# L9110_v1_0.net
KiCad netlist of a schematic drawn in EAGLE
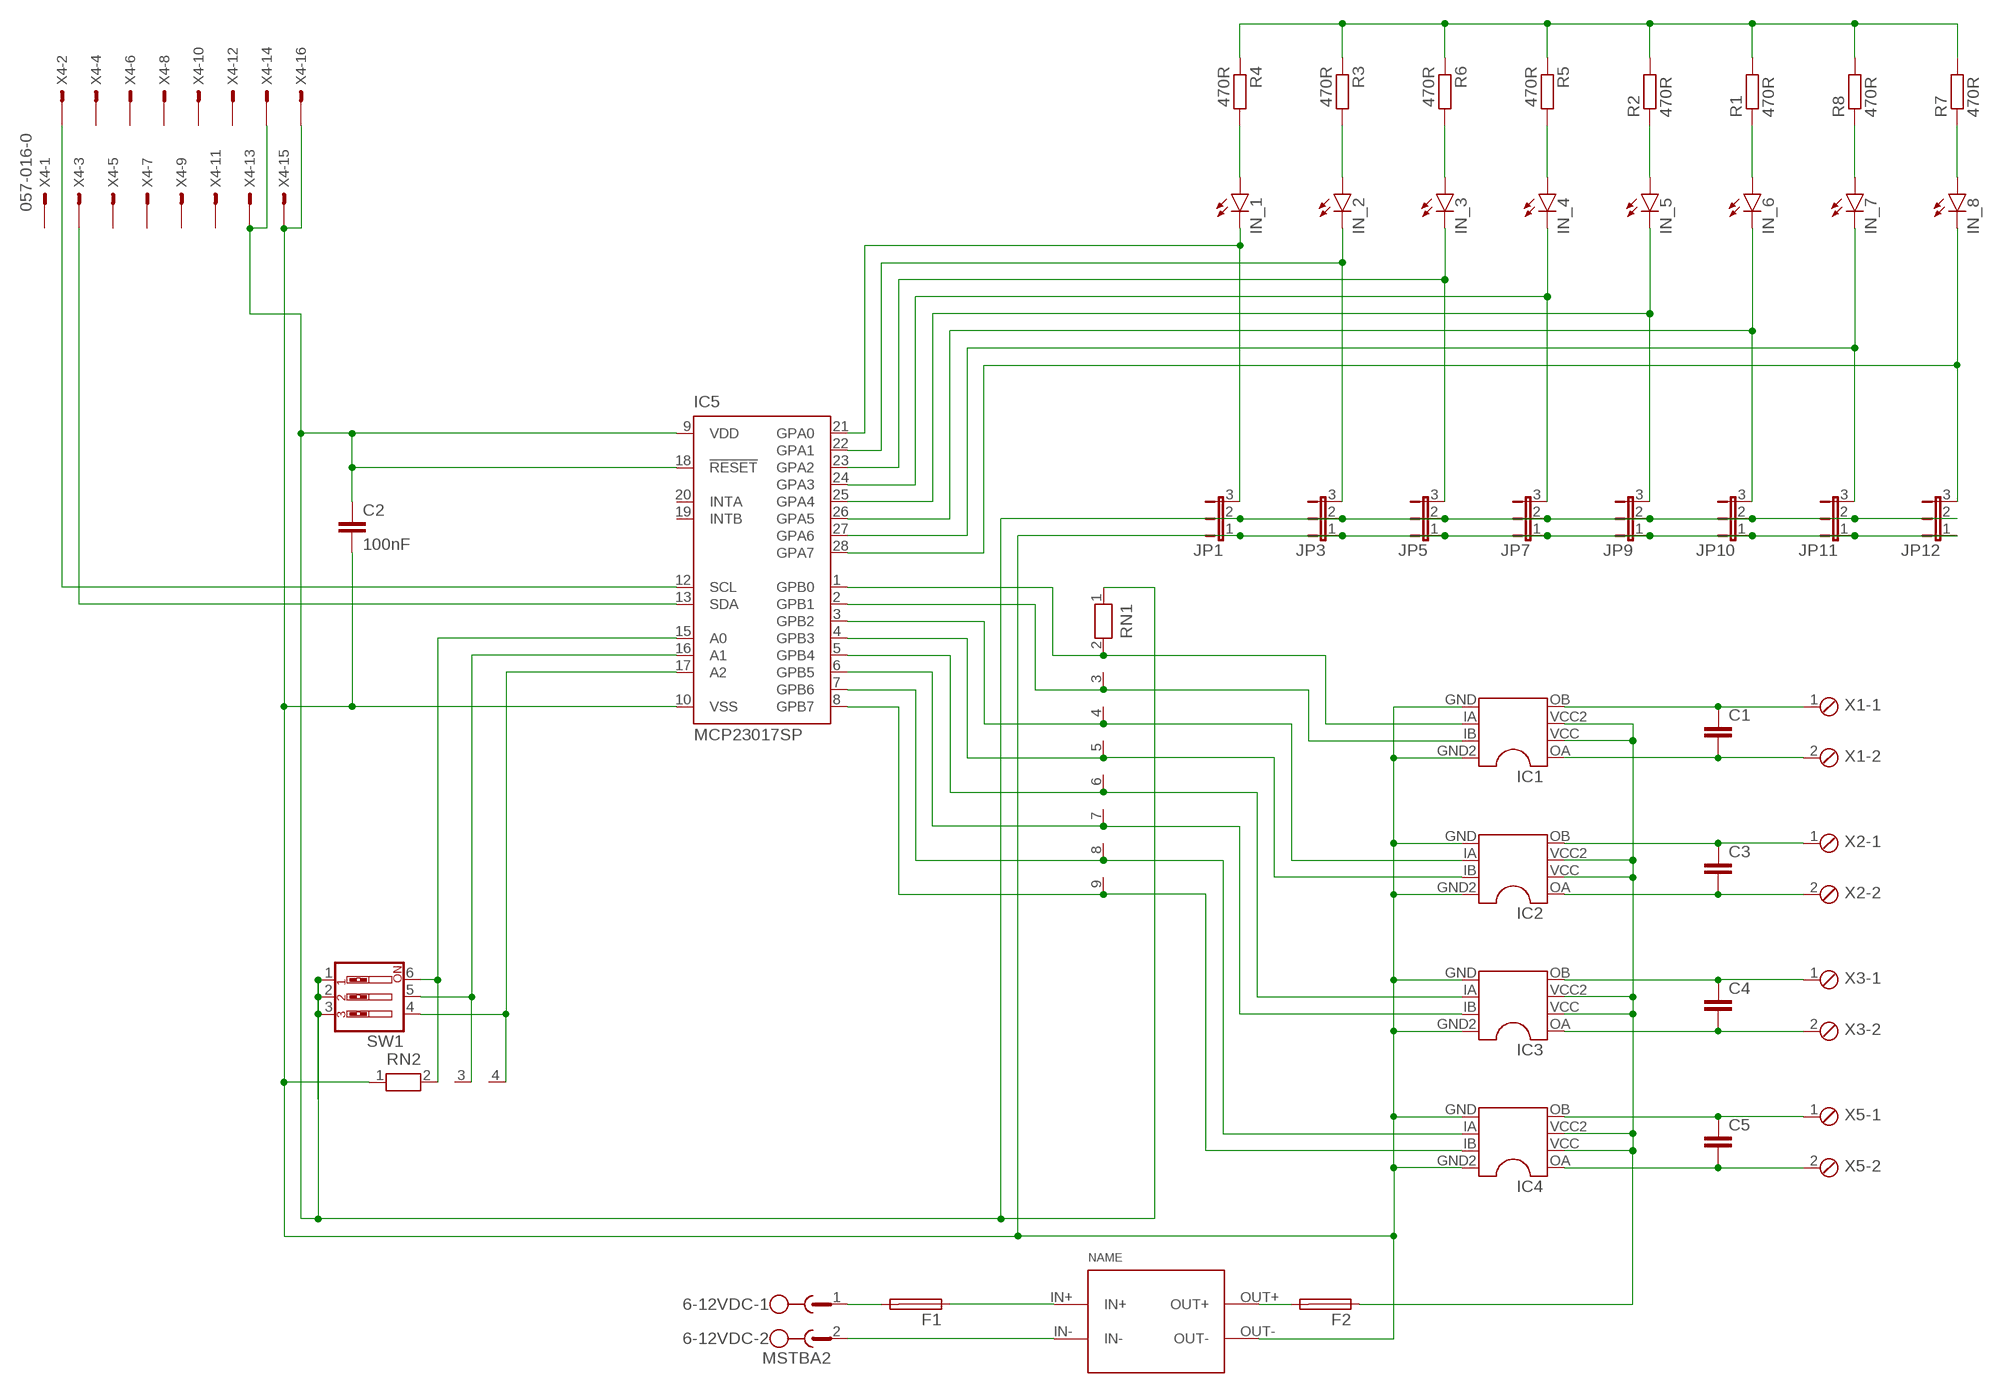
[diagram p0: schematic, sheet 1]

(export (version "E")
  (design (tool "Eeschema 10.0.6"))
  (components
    (comp (ref "6-12VDC")
      (value "MSTBA2")
      (footprint "eagle-import:MSTBA2")
      (fields (field (name "MF") "FARNELL") (field (name "MPN") "1757242"))
      (libsource (lib "eagle-import") (part "MSTBA2"))
    )
    (comp (ref "C1")
      (value "C-EU025-024X044")
      (footprint "eagle-import:C025-024X044")
      (libsource (lib "eagle-import") (part "C-EU025-024X044"))
    )
    (comp (ref "C2")
      (value "100nF")
      (footprint "eagle-import:C025-024X044")
      (libsource (lib "eagle-import") (part "C-EU025-024X044"))
    )
    (comp (ref "C3")
      (value "C-EU025-024X044")
      (footprint "eagle-import:C025-024X044")
      (libsource (lib "eagle-import") (part "C-EU025-024X044"))
    )
    (comp (ref "C4")
      (value "C-EU025-024X044")
      (footprint "eagle-import:C025-024X044")
      (libsource (lib "eagle-import") (part "C-EU025-024X044"))
    )
    (comp (ref "C5")
      (value "C-EU025-024X044")
      (footprint "eagle-import:C025-024X044")
      (libsource (lib "eagle-import") (part "C-EU025-024X044"))
    )
    (comp (ref "F1")
      (value "SH22,5A")
      (footprint "eagle-import:SH22,5A")
      (fields (field (name "MPN") "0031.7701.11"))
      (libsource (lib "eagle-import") (part "SH22,5A"))
    )
    (comp (ref "F2")
      (value "SH22,5A")
      (footprint "eagle-import:SH22,5A")
      (fields (field (name "MPN") "0031.7701.11"))
      (libsource (lib "eagle-import") (part "SH22,5A"))
    )
    (comp (ref "IC1")
      (value "L9110")
      (footprint "eagle-import:L9110")
      (libsource (lib "eagle-import") (part "L9110"))
    )
    (comp (ref "IC2")
      (value "L9110")
      (footprint "eagle-import:L9110")
      (libsource (lib "eagle-import") (part "L9110"))
    )
    (comp (ref "IC3")
      (value "L9110")
      (footprint "eagle-import:L9110")
      (libsource (lib "eagle-import") (part "L9110"))
    )
    (comp (ref "IC4")
      (value "L9110")
      (footprint "eagle-import:L9110")
      (libsource (lib "eagle-import") (part "L9110"))
    )
    (comp (ref "IC5")
      (value "MCP23017SP")
      (footprint "eagle-import:DIL28-3")
      (libsource (lib "eagle-import") (part "MCP23017SP"))
    )
    (comp (ref "IN_1")
      (value "LED3MM")
      (footprint "eagle-import:LED3MM")
      (libsource (lib "eagle-import") (part "LED3MM"))
    )
    (comp (ref "IN_2")
      (value "LED3MM")
      (footprint "eagle-import:LED3MM")
      (libsource (lib "eagle-import") (part "LED3MM"))
    )
    (comp (ref "IN_3")
      (value "LED3MM")
      (footprint "eagle-import:LED3MM")
      (libsource (lib "eagle-import") (part "LED3MM"))
    )
    (comp (ref "IN_4")
      (value "LED3MM")
      (footprint "eagle-import:LED3MM")
      (libsource (lib "eagle-import") (part "LED3MM"))
    )
    (comp (ref "IN_5")
      (value "LED3MM")
      (footprint "eagle-import:LED3MM")
      (libsource (lib "eagle-import") (part "LED3MM"))
    )
    (comp (ref "IN_6")
      (value "LED3MM")
      (footprint "eagle-import:LED3MM")
      (libsource (lib "eagle-import") (part "LED3MM"))
    )
    (comp (ref "IN_7")
      (value "LED3MM")
      (footprint "eagle-import:LED3MM")
      (libsource (lib "eagle-import") (part "LED3MM"))
    )
    (comp (ref "IN_8")
      (value "LED3MM")
      (footprint "eagle-import:LED3MM")
      (libsource (lib "eagle-import") (part "LED3MM"))
    )
    (comp (ref "JP1")
      (value "JP2E")
      (footprint "eagle-import:JP2")
      (libsource (lib "eagle-import") (part "JP2E"))
    )
    (comp (ref "JP3")
      (value "JP2E")
      (footprint "eagle-import:JP2")
      (libsource (lib "eagle-import") (part "JP2E"))
    )
    (comp (ref "JP5")
      (value "JP2E")
      (footprint "eagle-import:JP2")
      (libsource (lib "eagle-import") (part "JP2E"))
    )
    (comp (ref "JP7")
      (value "JP2E")
      (footprint "eagle-import:JP2")
      (libsource (lib "eagle-import") (part "JP2E"))
    )
    (comp (ref "JP9")
      (value "JP2E")
      (footprint "eagle-import:JP2")
      (libsource (lib "eagle-import") (part "JP2E"))
    )
    (comp (ref "JP10")
      (value "JP2E")
      (footprint "eagle-import:JP2")
      (libsource (lib "eagle-import") (part "JP2E"))
    )
    (comp (ref "JP11")
      (value "JP2E")
      (footprint "eagle-import:JP2")
      (libsource (lib "eagle-import") (part "JP2E"))
    )
    (comp (ref "JP12")
      (value "JP2E")
      (footprint "eagle-import:JP2")
      (libsource (lib "eagle-import") (part "JP2E"))
    )
    (comp (ref "R1")
      (value "470R")
      (footprint "eagle-import:0309_10")
      (libsource (lib "eagle-import") (part "R-EU_0309/10"))
    )
    (comp (ref "R2")
      (value "470R")
      (footprint "eagle-import:0309_10")
      (libsource (lib "eagle-import") (part "R-EU_0309/10"))
    )
    (comp (ref "R3")
      (value "470R")
      (footprint "eagle-import:0309_10")
      (libsource (lib "eagle-import") (part "R-EU_0309/10"))
    )
    (comp (ref "R4")
      (value "470R")
      (footprint "eagle-import:0309_10")
      (libsource (lib "eagle-import") (part "R-EU_0309/10"))
    )
    (comp (ref "R5")
      (value "470R")
      (footprint "eagle-import:0309_10")
      (libsource (lib "eagle-import") (part "R-EU_0309/10"))
    )
    (comp (ref "R6")
      (value "470R")
      (footprint "eagle-import:0309_10")
      (libsource (lib "eagle-import") (part "R-EU_0309/10"))
    )
    (comp (ref "R7")
      (value "470R")
      (footprint "eagle-import:0309_10")
      (libsource (lib "eagle-import") (part "R-EU_0309/10"))
    )
    (comp (ref "R8")
      (value "470R")
      (footprint "eagle-import:0309_10")
      (libsource (lib "eagle-import") (part "R-EU_0309/10"))
    )
    (comp (ref "RN1")
      (value "RN08")
      (footprint "eagle-import:RN-9")
      (libsource (lib "eagle-import") (part "RN08"))
    )
    (comp (ref "RN2")
      (value "RN03")
      (footprint "eagle-import:RN-3")
      (libsource (lib "eagle-import") (part "RN03"))
    )
    (comp (ref "SW1")
      (value "SW_DIP-3")
      (footprint "eagle-import:EDG-03")
      (libsource (lib "eagle-import") (part "SW_DIP-3"))
    )
    (comp (ref "U$2")
      (value "CP8-ADJ")
      (footprint "eagle-import:CP8-ADJ")
      (libsource (lib "eagle-import") (part "CP8-ADJ"))
    )
    (comp (ref "X1")
      (value "MPT2")
      (footprint "eagle-import:2POL254")
      (libsource (lib "eagle-import") (part "MPT2"))
    )
    (comp (ref "X2")
      (value "MPT2")
      (footprint "eagle-import:2POL254")
      (libsource (lib "eagle-import") (part "MPT2"))
    )
    (comp (ref "X3")
      (value "MPT2")
      (footprint "eagle-import:2POL254")
      (libsource (lib "eagle-import") (part "MPT2"))
    )
    (comp (ref "X4")
      (value "057-016-0")
      (footprint "eagle-import:057-016-0")
      (libsource (lib "eagle-import") (part "057-016-0"))
    )
    (comp (ref "X5")
      (value "MPT2")
      (footprint "eagle-import:2POL254")
      (libsource (lib "eagle-import") (part "MPT2"))
    )
  )
  (nets
    (net (code "1") (name "Net-(6-12VDC-Pad1)") (class "Default")
      (node (ref "6-12VDC") (pin "1") (pinfunction "1_1") (pintype "passive"))
      (node (ref "F1") (pin "2") (pinfunction "2_2") (pintype "passive"))
    )
    (net (code "2") (name "Net-(6-12VDCB-1)") (class "Default")
      (node (ref "6-12VDC") (pin "2") (pinfunction "1_2") (pintype "passive"))
      (node (ref "U$2") (pin "IN-") (pinfunction "IN-_IN-") (pintype "passive"))
    )
    (net (code "3") (name "Net-(F1-Pad1)") (class "Default")
      (node (ref "F1") (pin "1") (pinfunction "1_1") (pintype "passive"))
      (node (ref "U$2") (pin "IN+") (pinfunction "IN+_IN+") (pintype "passive"))
    )
    (net (code "4") (name "Net-(F2-Pad2)") (class "Default")
      (node (ref "F2") (pin "2") (pinfunction "2_2") (pintype "passive"))
      (node (ref "U$2") (pin "OUT+") (pinfunction "OUT+_OUT+") (pintype "passive"))
    )
    (net (code "5") (name "Net-(IC1-1)") (class "Default")
      (node (ref "C1") (pin "2") (pinfunction "2_2") (pintype "passive"))
      (node (ref "IC1") (pin "OA") (pinfunction "1_OA") (pintype "passive"))
      (node (ref "X1") (pin "2") (pinfunction "1_2") (pintype "passive"))
    )
    (net (code "6") (name "Net-(IC1-2)") (class "Default")
      (node (ref "F2") (pin "1") (pinfunction "1_1") (pintype "passive"))
      (node (ref "IC1") (pin "VCC") (pinfunction "2_VCC") (pintype "passive"))
      (node (ref "IC1") (pin "VCC2") (pinfunction "3_VCC2") (pintype "passive"))
      (node (ref "IC2") (pin "VCC") (pinfunction "2_VCC") (pintype "passive"))
      (node (ref "IC2") (pin "VCC2") (pinfunction "3_VCC2") (pintype "passive"))
      (node (ref "IC3") (pin "VCC") (pinfunction "2_VCC") (pintype "passive"))
      (node (ref "IC3") (pin "VCC2") (pinfunction "3_VCC2") (pintype "passive"))
      (node (ref "IC4") (pin "VCC") (pinfunction "2_VCC") (pintype "passive"))
      (node (ref "IC4") (pin "VCC2") (pinfunction "3_VCC2") (pintype "passive"))
    )
    (net (code "7") (name "Net-(IC1-4)") (class "Default")
      (node (ref "C1") (pin "1") (pinfunction "1_1") (pintype "passive"))
      (node (ref "IC1") (pin "OB") (pinfunction "4_OB") (pintype "passive"))
      (node (ref "X1") (pin "1") (pinfunction "1_1") (pintype "passive"))
    )
    (net (code "8") (name "Net-(IC1-5)") (class "Default")
      (node (ref "C2") (pin "2") (pinfunction "2_2") (pintype "passive"))
      (node (ref "IC1") (pin "GND") (pinfunction "5_GND") (pintype "passive"))
      (node (ref "IC1") (pin "GND2") (pinfunction "8_GND2") (pintype "passive"))
      (node (ref "IC2") (pin "GND") (pinfunction "5_GND") (pintype "passive"))
      (node (ref "IC2") (pin "GND2") (pinfunction "8_GND2") (pintype "passive"))
      (node (ref "IC3") (pin "GND") (pinfunction "5_GND") (pintype "passive"))
      (node (ref "IC3") (pin "GND2") (pinfunction "8_GND2") (pintype "passive"))
      (node (ref "IC4") (pin "GND") (pinfunction "5_GND") (pintype "passive"))
      (node (ref "IC4") (pin "GND2") (pinfunction "8_GND2") (pintype "passive"))
      (node (ref "IC5") (pin "10") (pinfunction "VSS_10") (pintype "power_in"))
      (node (ref "JP1") (pin "1") (pinfunction "1_1") (pintype "passive"))
      (node (ref "JP10") (pin "1") (pinfunction "1_1") (pintype "passive"))
      (node (ref "JP11") (pin "1") (pinfunction "1_1") (pintype "passive"))
      (node (ref "JP12") (pin "1") (pinfunction "1_1") (pintype "passive"))
      (node (ref "JP3") (pin "1") (pinfunction "1_1") (pintype "passive"))
      (node (ref "JP5") (pin "1") (pinfunction "1_1") (pintype "passive"))
      (node (ref "JP7") (pin "1") (pinfunction "1_1") (pintype "passive"))
      (node (ref "JP9") (pin "1") (pinfunction "1_1") (pintype "passive"))
      (node (ref "RN2") (pin "1") (pinfunction "1_1") (pintype "passive"))
      (node (ref "U$2") (pin "OUT-") (pinfunction "OUT-_OUT-") (pintype "passive"))
      (node (ref "X4") (pin "15") (pinfunction "S_15") (pintype "passive"))
      (node (ref "X4") (pin "16") (pinfunction "S_16") (pintype "passive"))
    )
    (net (code "9") (name "Net-(IC1-6)") (class "Default")
      (node (ref "IC1") (pin "IA") (pinfunction "6_IA") (pintype "passive"))
      (node (ref "IC5") (pin "1") (pinfunction "GPB0_1") (pintype "bidirectional"))
      (node (ref "RN1") (pin "2") (pinfunction "2_2") (pintype "passive"))
    )
    (net (code "10") (name "Net-(IC1-7)") (class "Default")
      (node (ref "IC1") (pin "IB") (pinfunction "7_IB") (pintype "passive"))
      (node (ref "IC5") (pin "2") (pinfunction "GPB1_2") (pintype "bidirectional"))
      (node (ref "RN1") (pin "3") (pinfunction "3_3") (pintype "passive"))
    )
    (net (code "11") (name "Net-(IC2-1)") (class "Default")
      (node (ref "C3") (pin "2") (pinfunction "2_2") (pintype "passive"))
      (node (ref "IC2") (pin "OA") (pinfunction "1_OA") (pintype "passive"))
      (node (ref "X2") (pin "2") (pinfunction "1_2") (pintype "passive"))
    )
    (net (code "12") (name "Net-(IC2-4)") (class "Default")
      (node (ref "C3") (pin "1") (pinfunction "1_1") (pintype "passive"))
      (node (ref "IC2") (pin "OB") (pinfunction "4_OB") (pintype "passive"))
      (node (ref "X2") (pin "1") (pinfunction "1_1") (pintype "passive"))
    )
    (net (code "13") (name "Net-(IC2-6)") (class "Default")
      (node (ref "IC2") (pin "IA") (pinfunction "6_IA") (pintype "passive"))
      (node (ref "IC5") (pin "3") (pinfunction "GPB2_3") (pintype "bidirectional"))
      (node (ref "RN1") (pin "4") (pinfunction "4_4") (pintype "passive"))
    )
    (net (code "14") (name "Net-(IC2-7)") (class "Default")
      (node (ref "IC2") (pin "IB") (pinfunction "7_IB") (pintype "passive"))
      (node (ref "IC5") (pin "4") (pinfunction "GPB3_4") (pintype "bidirectional"))
      (node (ref "RN1") (pin "5") (pinfunction "5_5") (pintype "passive"))
    )
    (net (code "15") (name "Net-(IC3-1)") (class "Default")
      (node (ref "C4") (pin "2") (pinfunction "2_2") (pintype "passive"))
      (node (ref "IC3") (pin "OA") (pinfunction "1_OA") (pintype "passive"))
      (node (ref "X3") (pin "2") (pinfunction "1_2") (pintype "passive"))
    )
    (net (code "16") (name "Net-(IC3-4)") (class "Default")
      (node (ref "C4") (pin "1") (pinfunction "1_1") (pintype "passive"))
      (node (ref "IC3") (pin "OB") (pinfunction "4_OB") (pintype "passive"))
      (node (ref "X3") (pin "1") (pinfunction "1_1") (pintype "passive"))
    )
    (net (code "17") (name "Net-(IC3-6)") (class "Default")
      (node (ref "IC3") (pin "IA") (pinfunction "6_IA") (pintype "passive"))
      (node (ref "IC5") (pin "5") (pinfunction "GPB4_5") (pintype "bidirectional"))
      (node (ref "RN1") (pin "6") (pinfunction "6_6") (pintype "passive"))
    )
    (net (code "18") (name "Net-(IC3-7)") (class "Default")
      (node (ref "IC3") (pin "IB") (pinfunction "7_IB") (pintype "passive"))
      (node (ref "IC5") (pin "6") (pinfunction "GPB5_6") (pintype "bidirectional"))
      (node (ref "RN1") (pin "7") (pinfunction "7_7") (pintype "passive"))
    )
    (net (code "19") (name "Net-(IC4-1)") (class "Default")
      (node (ref "C5") (pin "2") (pinfunction "2_2") (pintype "passive"))
      (node (ref "IC4") (pin "OA") (pinfunction "1_OA") (pintype "passive"))
      (node (ref "X5") (pin "2") (pinfunction "1_2") (pintype "passive"))
    )
    (net (code "20") (name "Net-(IC4-4)") (class "Default")
      (node (ref "C5") (pin "1") (pinfunction "1_1") (pintype "passive"))
      (node (ref "IC4") (pin "OB") (pinfunction "4_OB") (pintype "passive"))
      (node (ref "X5") (pin "1") (pinfunction "1_1") (pintype "passive"))
    )
    (net (code "21") (name "Net-(IC4-6)") (class "Default")
      (node (ref "IC4") (pin "IA") (pinfunction "6_IA") (pintype "passive"))
      (node (ref "IC5") (pin "7") (pinfunction "GPB6_7") (pintype "bidirectional"))
      (node (ref "RN1") (pin "8") (pinfunction "8_8") (pintype "passive"))
    )
    (net (code "22") (name "Net-(IC4-7)") (class "Default")
      (node (ref "IC4") (pin "IB") (pinfunction "7_IB") (pintype "passive"))
      (node (ref "IC5") (pin "8") (pinfunction "GPB7_8") (pintype "bidirectional"))
      (node (ref "RN1") (pin "9") (pinfunction "9_9") (pintype "passive"))
    )
    (net (code "23") (name "Net-(IC5-A0)") (class "Default")
      (node (ref "IC5") (pin "15") (pinfunction "A0_15") (pintype "input"))
      (node (ref "RN2") (pin "2") (pinfunction "2_2") (pintype "passive"))
      (node (ref "SW1") (pin "6") (pinfunction "6_6") (pintype "passive"))
    )
    (net (code "24") (name "Net-(IC5-A1)") (class "Default")
      (node (ref "IC5") (pin "16") (pinfunction "A1_16") (pintype "input"))
      (node (ref "RN2") (pin "3") (pinfunction "3_3") (pintype "passive"))
      (node (ref "SW1") (pin "5") (pinfunction "5_5") (pintype "passive"))
    )
    (net (code "25") (name "Net-(IC5-A2)") (class "Default")
      (node (ref "IC5") (pin "17") (pinfunction "A2_17") (pintype "input"))
      (node (ref "RN2") (pin "4") (pinfunction "4_4") (pintype "passive"))
      (node (ref "SW1") (pin "4") (pinfunction "4_4") (pintype "passive"))
    )
    (net (code "26") (name "Net-(IC5-GPA0)") (class "Default")
      (node (ref "IC5") (pin "21") (pinfunction "GPA0_21") (pintype "bidirectional"))
      (node (ref "IN_1") (pin "K") (pinfunction "C_K") (pintype "passive"))
      (node (ref "JP1") (pin "3") (pinfunction "3_3") (pintype "passive"))
    )
    (net (code "27") (name "Net-(IC5-GPA1)") (class "Default")
      (node (ref "IC5") (pin "22") (pinfunction "GPA1_22") (pintype "bidirectional"))
      (node (ref "IN_2") (pin "K") (pinfunction "C_K") (pintype "passive"))
      (node (ref "JP3") (pin "3") (pinfunction "3_3") (pintype "passive"))
    )
    (net (code "28") (name "Net-(IC5-GPA2)") (class "Default")
      (node (ref "IC5") (pin "23") (pinfunction "GPA2_23") (pintype "bidirectional"))
      (node (ref "IN_3") (pin "K") (pinfunction "C_K") (pintype "passive"))
      (node (ref "JP5") (pin "3") (pinfunction "3_3") (pintype "passive"))
    )
    (net (code "29") (name "Net-(IC5-GPA3)") (class "Default")
      (node (ref "IC5") (pin "24") (pinfunction "GPA3_24") (pintype "bidirectional"))
      (node (ref "IN_4") (pin "K") (pinfunction "C_K") (pintype "passive"))
      (node (ref "JP7") (pin "3") (pinfunction "3_3") (pintype "passive"))
    )
    (net (code "30") (name "Net-(IC5-GPA4)") (class "Default")
      (node (ref "IC5") (pin "25") (pinfunction "GPA4_25") (pintype "bidirectional"))
      (node (ref "IN_5") (pin "K") (pinfunction "C_K") (pintype "passive"))
      (node (ref "JP9") (pin "3") (pinfunction "3_3") (pintype "passive"))
    )
    (net (code "31") (name "Net-(IC5-GPA5)") (class "Default")
      (node (ref "IC5") (pin "26") (pinfunction "GPA5_26") (pintype "bidirectional"))
      (node (ref "IN_6") (pin "K") (pinfunction "C_K") (pintype "passive"))
      (node (ref "JP10") (pin "3") (pinfunction "3_3") (pintype "passive"))
    )
    (net (code "32") (name "Net-(IC5-GPA6)") (class "Default")
      (node (ref "IC5") (pin "27") (pinfunction "GPA6_27") (pintype "bidirectional"))
      (node (ref "IN_7") (pin "K") (pinfunction "C_K") (pintype "passive"))
      (node (ref "JP11") (pin "3") (pinfunction "3_3") (pintype "passive"))
    )
    (net (code "33") (name "Net-(IC5-GPA7)") (class "Default")
      (node (ref "IC5") (pin "28") (pinfunction "GPA7_28") (pintype "bidirectional"))
      (node (ref "IN_8") (pin "K") (pinfunction "C_K") (pintype "passive"))
      (node (ref "JP12") (pin "3") (pinfunction "3_3") (pintype "passive"))
    )
    (net (code "34") (name "Net-(IC5-SCL)") (class "Default")
      (node (ref "IC5") (pin "12") (pinfunction "SCL_12") (pintype "input"))
      (node (ref "X4") (pin "2") (pinfunction "S_2") (pintype "passive"))
    )
    (net (code "35") (name "Net-(IC5-SDA)") (class "Default")
      (node (ref "IC5") (pin "13") (pinfunction "SDA_13") (pintype "bidirectional"))
      (node (ref "X4") (pin "3") (pinfunction "S_3") (pintype "passive"))
    )
    (net (code "36") (name "Net-(IC5-VDD)") (class "Default")
      (node (ref "C2") (pin "1") (pinfunction "1_1") (pintype "passive"))
      (node (ref "IC5") (pin "18") (pinfunction "~{RESET}_18") (pintype "input"))
      (node (ref "IC5") (pin "9") (pinfunction "VDD_9") (pintype "power_in"))
      (node (ref "JP1") (pin "2") (pinfunction "2_2") (pintype "passive"))
      (node (ref "JP10") (pin "2") (pinfunction "2_2") (pintype "passive"))
      (node (ref "JP11") (pin "2") (pinfunction "2_2") (pintype "passive"))
      (node (ref "JP12") (pin "2") (pinfunction "2_2") (pintype "passive"))
      (node (ref "JP3") (pin "2") (pinfunction "2_2") (pintype "passive"))
      (node (ref "JP5") (pin "2") (pinfunction "2_2") (pintype "passive"))
      (node (ref "JP7") (pin "2") (pinfunction "2_2") (pintype "passive"))
      (node (ref "JP9") (pin "2") (pinfunction "2_2") (pintype "passive"))
      (node (ref "RN1") (pin "1") (pinfunction "1_1") (pintype "passive"))
      (node (ref "SW1") (pin "1") (pinfunction "1_1") (pintype "passive"))
      (node (ref "SW1") (pin "2") (pinfunction "2_2") (pintype "passive"))
      (node (ref "SW1") (pin "3") (pinfunction "3_3") (pintype "passive"))
      (node (ref "X4") (pin "13") (pinfunction "S_13") (pintype "passive"))
      (node (ref "X4") (pin "14") (pinfunction "S_14") (pintype "passive"))
    )
    (net (code "37") (name "Net-(IN_1-PadA)") (class "Default")
      (node (ref "IN_1") (pin "A") (pinfunction "A_A") (pintype "passive"))
      (node (ref "R4") (pin "2") (pinfunction "2_2") (pintype "passive"))
    )
    (net (code "38") (name "Net-(IN_2-PadA)") (class "Default")
      (node (ref "IN_2") (pin "A") (pinfunction "A_A") (pintype "passive"))
      (node (ref "R3") (pin "2") (pinfunction "2_2") (pintype "passive"))
    )
    (net (code "39") (name "Net-(IN_3-PadA)") (class "Default")
      (node (ref "IN_3") (pin "A") (pinfunction "A_A") (pintype "passive"))
      (node (ref "R6") (pin "2") (pinfunction "2_2") (pintype "passive"))
    )
    (net (code "40") (name "Net-(IN_4-PadA)") (class "Default")
      (node (ref "IN_4") (pin "A") (pinfunction "A_A") (pintype "passive"))
      (node (ref "R5") (pin "2") (pinfunction "2_2") (pintype "passive"))
    )
    (net (code "41") (name "Net-(IN_5-PadA)") (class "Default")
      (node (ref "IN_5") (pin "A") (pinfunction "A_A") (pintype "passive"))
      (node (ref "R2") (pin "1") (pinfunction "1_1") (pintype "passive"))
    )
    (net (code "42") (name "Net-(IN_6-PadA)") (class "Default")
      (node (ref "IN_6") (pin "A") (pinfunction "A_A") (pintype "passive"))
      (node (ref "R1") (pin "1") (pinfunction "1_1") (pintype "passive"))
    )
    (net (code "43") (name "Net-(IN_7-PadA)") (class "Default")
      (node (ref "IN_7") (pin "A") (pinfunction "A_A") (pintype "passive"))
      (node (ref "R8") (pin "1") (pinfunction "1_1") (pintype "passive"))
    )
    (net (code "44") (name "Net-(IN_8-PadA)") (class "Default")
      (node (ref "IN_8") (pin "A") (pinfunction "A_A") (pintype "passive"))
      (node (ref "R7") (pin "1") (pinfunction "1_1") (pintype "passive"))
    )
    (net (code "45") (name "Net-(R1-Pad2)") (class "Default")
      (node (ref "R1") (pin "2") (pinfunction "2_2") (pintype "passive"))
      (node (ref "R2") (pin "2") (pinfunction "2_2") (pintype "passive"))
      (node (ref "R3") (pin "1") (pinfunction "1_1") (pintype "passive"))
      (node (ref "R4") (pin "1") (pinfunction "1_1") (pintype "passive"))
      (node (ref "R5") (pin "1") (pinfunction "1_1") (pintype "passive"))
      (node (ref "R6") (pin "1") (pinfunction "1_1") (pintype "passive"))
      (node (ref "R7") (pin "2") (pinfunction "2_2") (pintype "passive"))
      (node (ref "R8") (pin "2") (pinfunction "2_2") (pintype "passive"))
    )
    (net (code "46") (name "unconnected-(IC5-INTA-Pad20)") (class "Default")
      (node (ref "IC5") (pin "20") (pinfunction "INTA_20") (pintype "output"))
    )
    (net (code "47") (name "unconnected-(IC5-INTB-Pad19)") (class "Default")
      (node (ref "IC5") (pin "19") (pinfunction "INTB_19") (pintype "output"))
    )
    (net (code "48") (name "unconnected-(X4A-S-Pad1)") (class "Default")
      (node (ref "X4") (pin "1") (pinfunction "S_1") (pintype "passive"))
    )
    (net (code "49") (name "unconnected-(X4B-S-Pad10)") (class "Default")
      (node (ref "X4") (pin "10") (pinfunction "S_10") (pintype "passive"))
    )
    (net (code "50") (name "unconnected-(X4C-S-Pad11)") (class "Default")
      (node (ref "X4") (pin "11") (pinfunction "S_11") (pintype "passive"))
    )
    (net (code "51") (name "unconnected-(X4D-S-Pad12)") (class "Default")
      (node (ref "X4") (pin "12") (pinfunction "S_12") (pintype "passive"))
    )
    (net (code "52") (name "unconnected-(X4K-S-Pad4)") (class "Default")
      (node (ref "X4") (pin "4") (pinfunction "S_4") (pintype "passive"))
    )
    (net (code "53") (name "unconnected-(X4L-S-Pad5)") (class "Default")
      (node (ref "X4") (pin "5") (pinfunction "S_5") (pintype "passive"))
    )
    (net (code "54") (name "unconnected-(X4M-S-Pad6)") (class "Default")
      (node (ref "X4") (pin "6") (pinfunction "S_6") (pintype "passive"))
    )
    (net (code "55") (name "unconnected-(X4N-S-Pad7)") (class "Default")
      (node (ref "X4") (pin "7") (pinfunction "S_7") (pintype "passive"))
    )
    (net (code "56") (name "unconnected-(X4O-S-Pad8)") (class "Default")
      (node (ref "X4") (pin "8") (pinfunction "S_8") (pintype "passive"))
    )
    (net (code "57") (name "unconnected-(X4P-S-Pad9)") (class "Default")
      (node (ref "X4") (pin "9") (pinfunction "S_9") (pintype "passive"))
    )
  )
)
